# batteryholder2S6P_revD.net
KiCad netlist of a schematic drawn in EAGLE
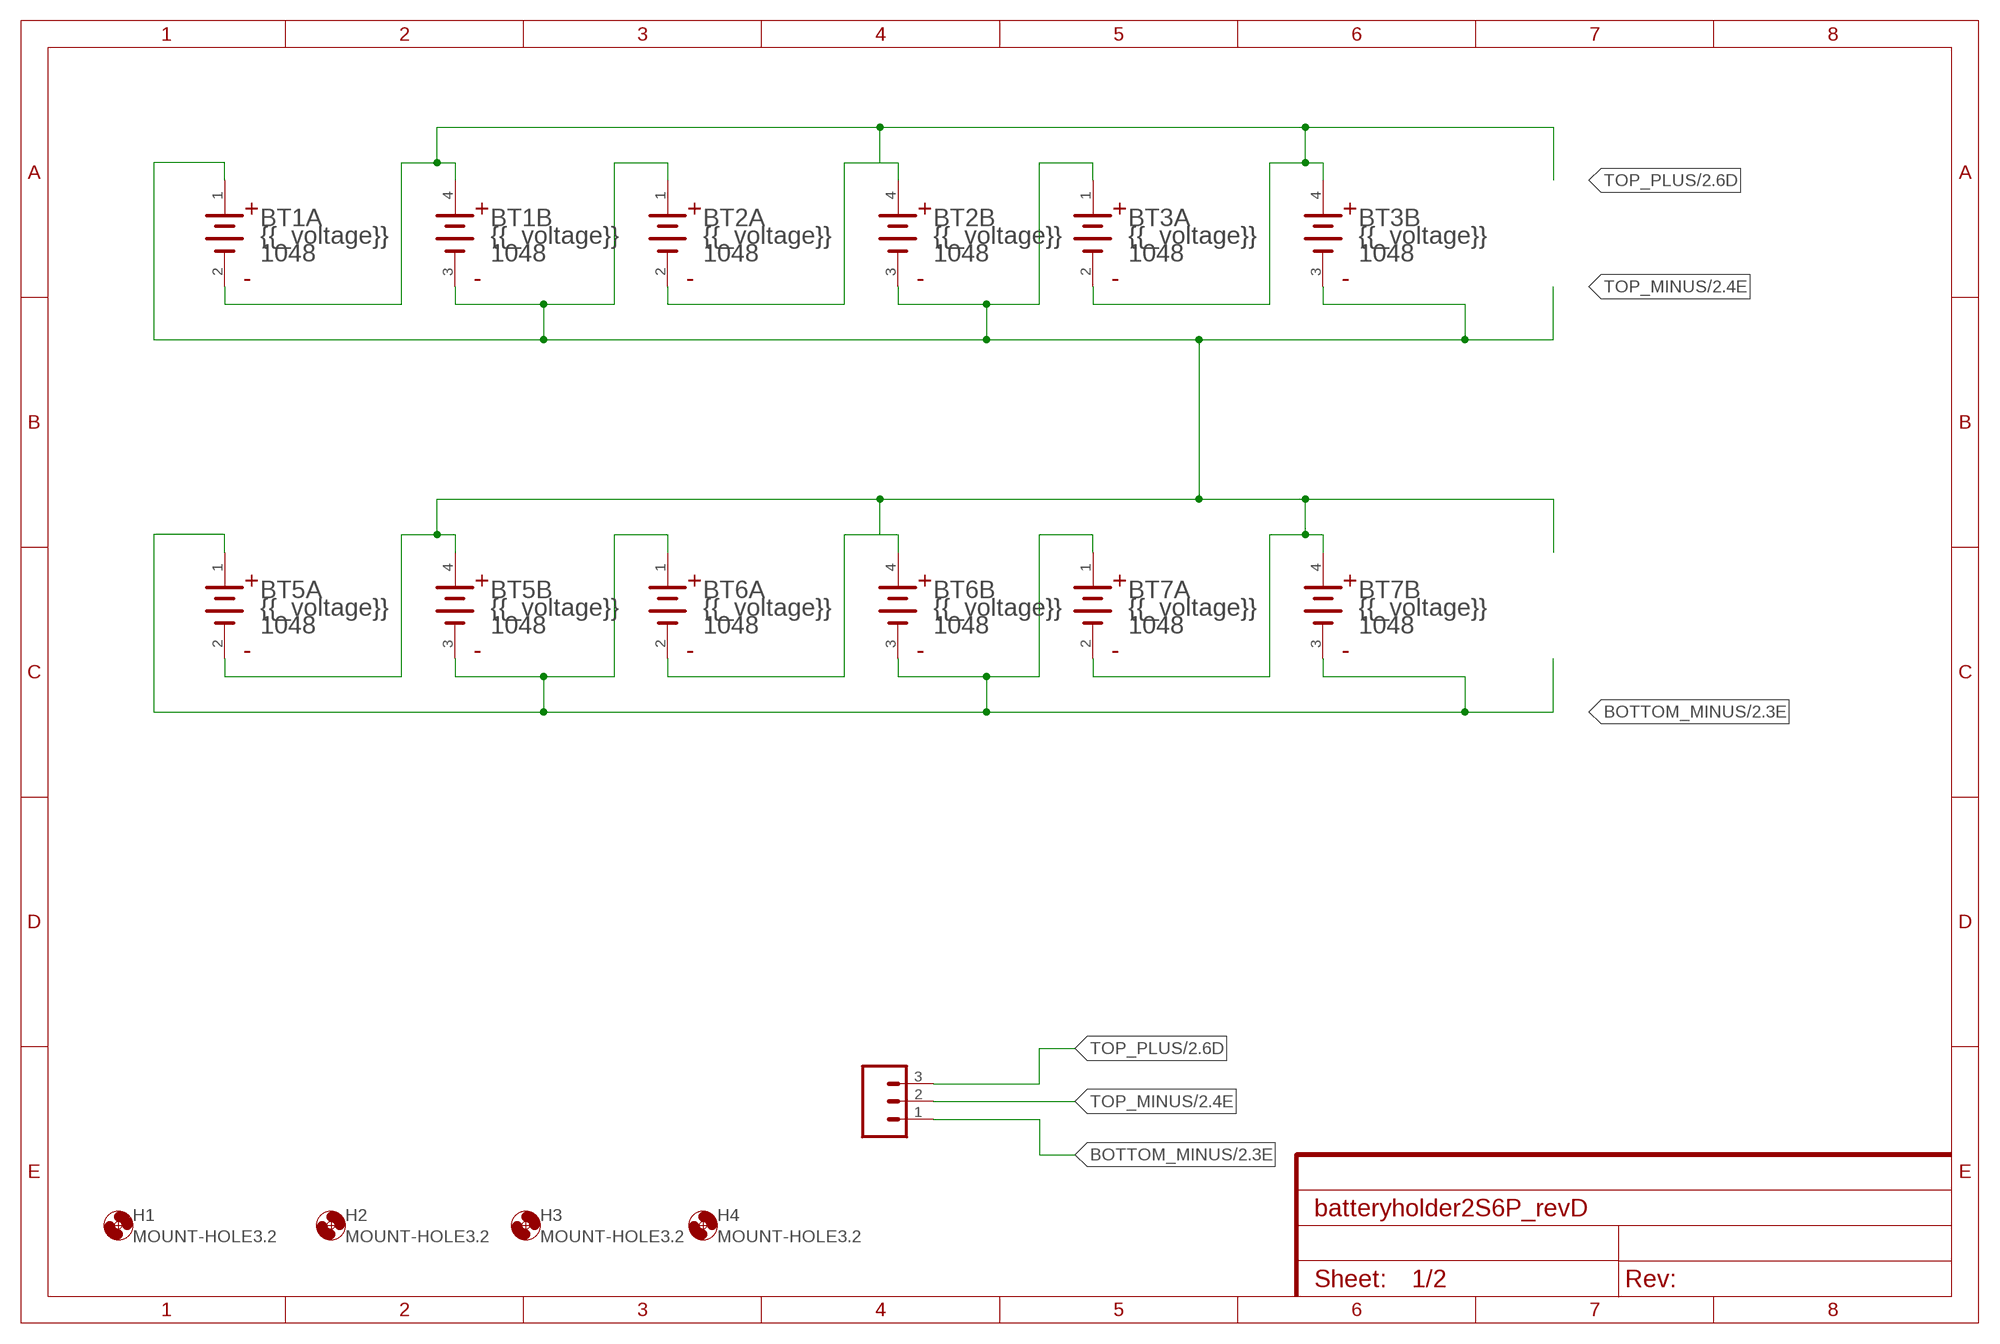
[diagram p0: schematic, sheet 1]
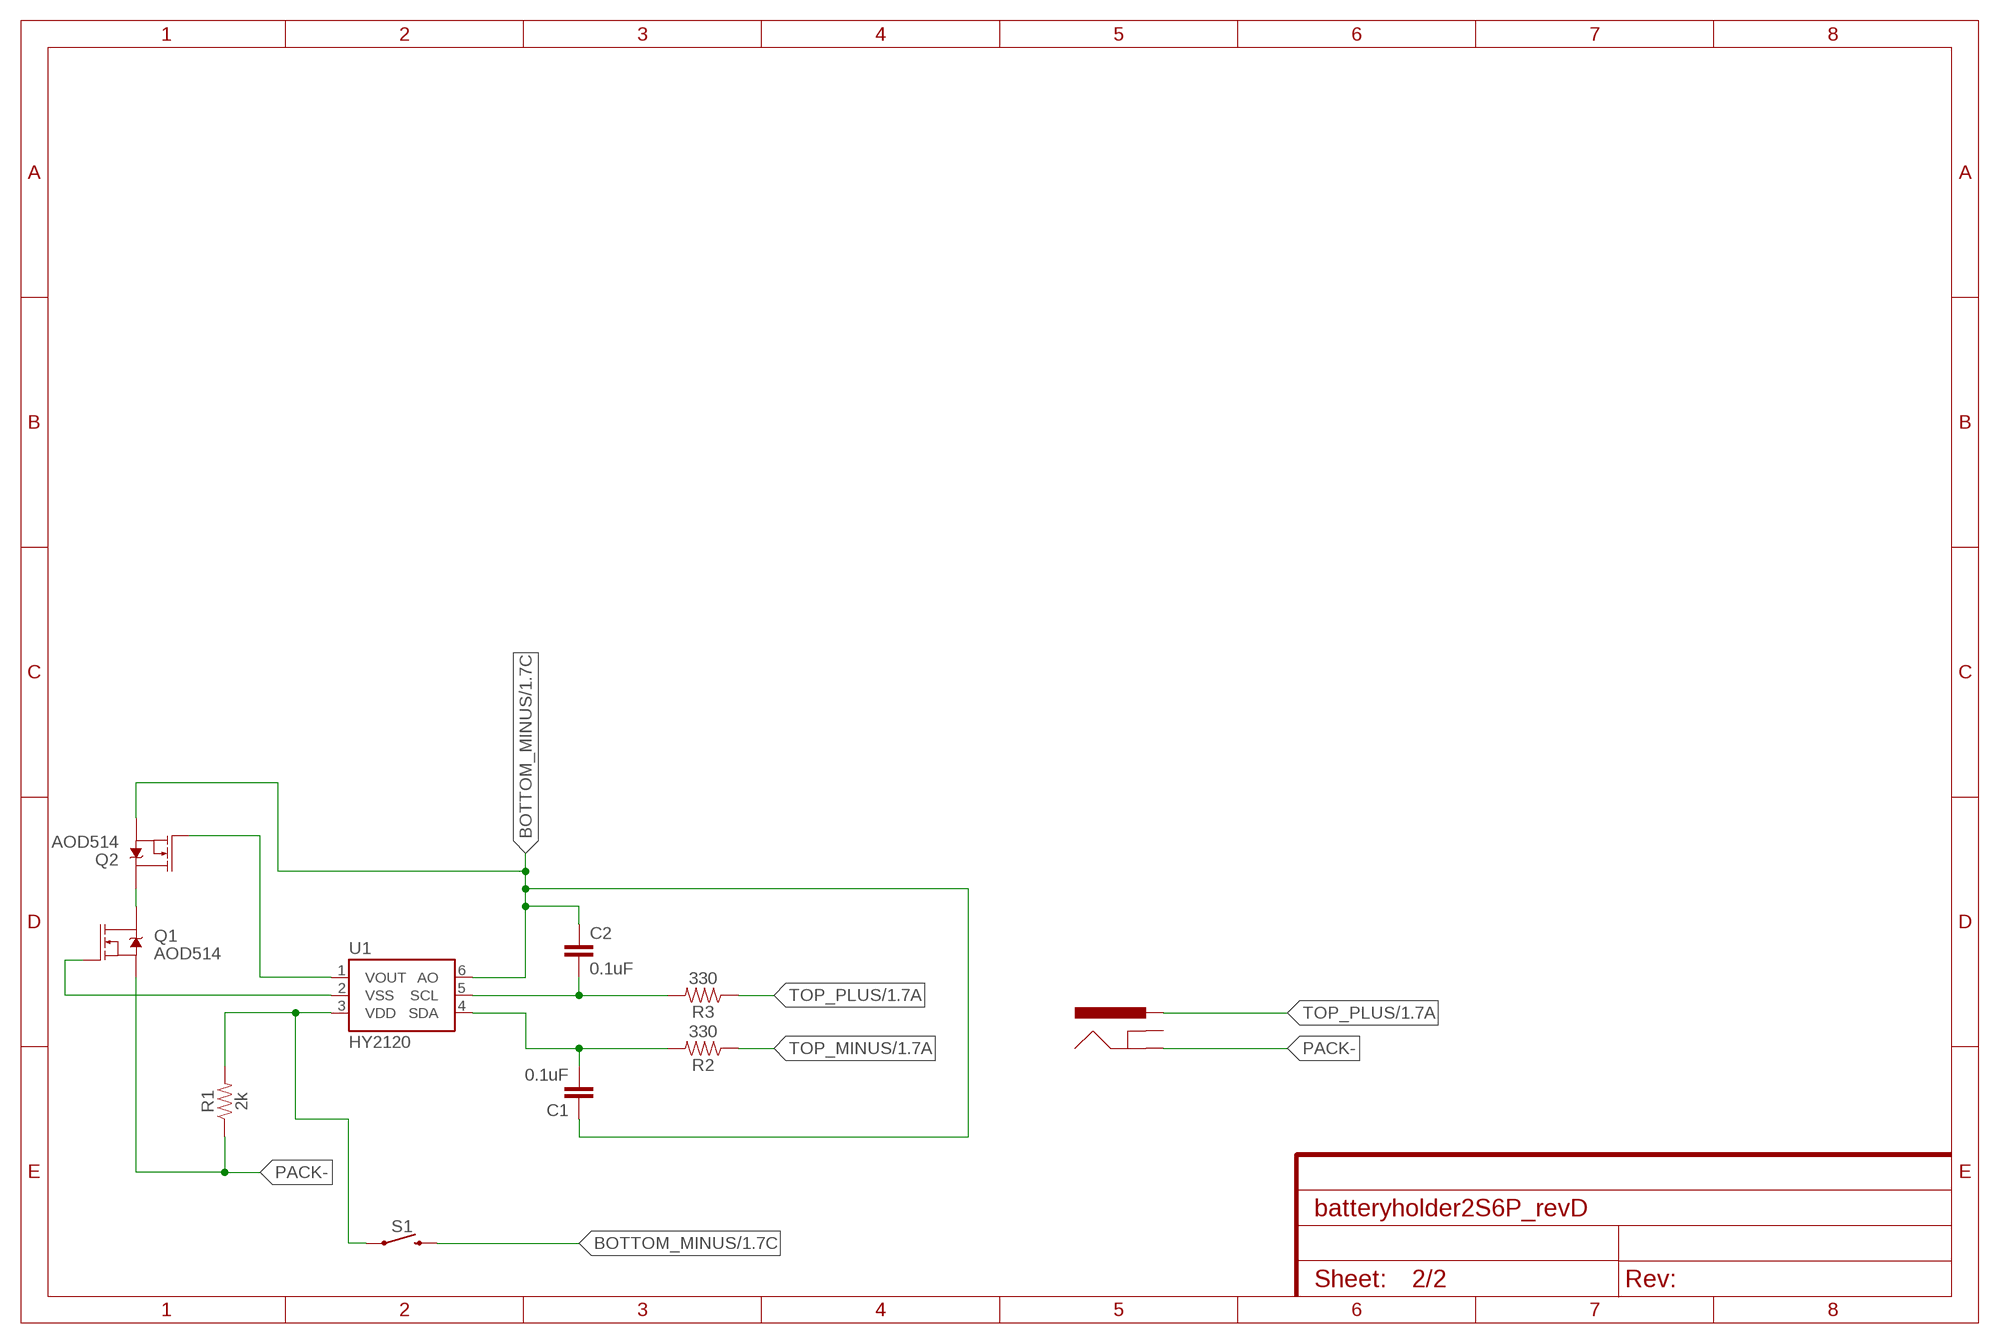
[diagram p1: schematic, sheet 2]

(export (version "E")
  (design (tool "Eeschema 10.0.6"))
  (components
    (comp (ref "C1")
      (value "0.1uF")
      (footprint "eagle-import:1206")
      (libsource (lib "eagle-import") (part "1.0UF-1206-50V-10%"))
    )
    (comp (ref "C2")
      (value "0.1uF")
      (footprint "eagle-import:1206")
      (libsource (lib "eagle-import") (part "1.0UF-1206-50V-10%"))
    )
    (comp (ref "J2")
      (value "POWER_JACKPTH_BREAD")
      (footprint "eagle-import:POWER_JACK_PTH_BREAD")
      (libsource (lib "eagle-import") (part "POWER_JACKPTH_BREAD"))
    )
    (comp (ref "Q1")
      (value "AOD514")
      (footprint "eagle-import:DPAK")
      (libsource (lib "eagle-import") (part "MOSFET-NCH-FDD8780"))
    )
    (comp (ref "Q2")
      (value "AOD514")
      (footprint "eagle-import:DPAK")
      (libsource (lib "eagle-import") (part "MOSFET-NCH-FDD8780"))
    )
    (comp (ref "R1")
      (value "2k")
      (footprint "eagle-import:1206")
      (libsource (lib "eagle-import") (part "RESISTOR1206"))
    )
    (comp (ref "R2")
      (value "330")
      (footprint "eagle-import:1206")
      (libsource (lib "eagle-import") (part "RESISTOR1206"))
    )
    (comp (ref "R3")
      (value "330")
      (footprint "eagle-import:1206")
      (libsource (lib "eagle-import") (part "RESISTOR1206"))
    )
    (comp (ref "S1")
      (value "MOMENTARY-SWITCH-SPST-PTH-6.0MM")
      (footprint "eagle-import:TACTILE_SWITCH_PTH_6.0MM")
      (libsource (lib "eagle-import") (part "MOMENTARY-SWITCH-SPST-PTH-6.0MM"))
    )
    (comp (ref "U1")
      (value "HY2120")
      (footprint "eagle-import:SOT23-6")
      (libsource (lib "eagle-import") (part "MCP4725SOT-23"))
    )
    (comp (ref "BT1")
      (value "KEYSTONE_1048KEYSTONE_1048_0_0")
      (footprint "eagle-import:KEYSTONE_1048_0")
      (fields
        (field (name "DIGIKEY_PART_NUMBER") "36-1048-ND")
        (field (name "MF") "Keystone")
        (field (name "MOUSER_PART_NUMBER") "534-1048")
      )
      (libsource (lib "eagle-import") (part "KEYSTONE_1048KEYSTONE_1048_0_0"))
    )
    (comp (ref "BT2")
      (value "KEYSTONE_1048KEYSTONE_1048_0_0")
      (footprint "eagle-import:KEYSTONE_1048_0")
      (fields
        (field (name "DIGIKEY_PART_NUMBER") "36-1048-ND")
        (field (name "MF") "Keystone")
        (field (name "MOUSER_PART_NUMBER") "534-1048")
      )
      (libsource (lib "eagle-import") (part "KEYSTONE_1048KEYSTONE_1048_0_0"))
    )
    (comp (ref "BT3")
      (value "KEYSTONE_1048KEYSTONE_1048_0_0")
      (footprint "eagle-import:KEYSTONE_1048_0")
      (fields
        (field (name "DIGIKEY_PART_NUMBER") "36-1048-ND")
        (field (name "MF") "Keystone")
        (field (name "MOUSER_PART_NUMBER") "534-1048")
      )
      (libsource (lib "eagle-import") (part "KEYSTONE_1048KEYSTONE_1048_0_0"))
    )
    (comp (ref "BT5")
      (value "KEYSTONE_1048KEYSTONE_1048_0_0")
      (footprint "eagle-import:KEYSTONE_1048_0")
      (fields
        (field (name "DIGIKEY_PART_NUMBER") "36-1048-ND")
        (field (name "MF") "Keystone")
        (field (name "MOUSER_PART_NUMBER") "534-1048")
      )
      (libsource (lib "eagle-import") (part "KEYSTONE_1048KEYSTONE_1048_0_0"))
    )
    (comp (ref "BT6")
      (value "KEYSTONE_1048KEYSTONE_1048_0_0")
      (footprint "eagle-import:KEYSTONE_1048_0")
      (fields
        (field (name "DIGIKEY_PART_NUMBER") "36-1048-ND")
        (field (name "MF") "Keystone")
        (field (name "MOUSER_PART_NUMBER") "534-1048")
      )
      (libsource (lib "eagle-import") (part "KEYSTONE_1048KEYSTONE_1048_0_0"))
    )
    (comp (ref "BT7")
      (value "KEYSTONE_1048KEYSTONE_1048_0_0")
      (footprint "eagle-import:KEYSTONE_1048_0")
      (fields
        (field (name "DIGIKEY_PART_NUMBER") "36-1048-ND")
        (field (name "MF") "Keystone")
        (field (name "MOUSER_PART_NUMBER") "534-1048")
      )
      (libsource (lib "eagle-import") (part "KEYSTONE_1048KEYSTONE_1048_0_0"))
    )
    (comp (ref "H1")
      (value "MOUNT-HOLE3.2")
      (footprint "eagle-import:3,2")
      (libsource (lib "eagle-import") (part "MOUNT-HOLE3.2"))
    )
    (comp (ref "H2")
      (value "MOUNT-HOLE3.2")
      (footprint "eagle-import:3,2")
      (libsource (lib "eagle-import") (part "MOUNT-HOLE3.2"))
    )
    (comp (ref "H3")
      (value "MOUNT-HOLE3.2")
      (footprint "eagle-import:3,2")
      (libsource (lib "eagle-import") (part "MOUNT-HOLE3.2"))
    )
    (comp (ref "H4")
      (value "MOUNT-HOLE3.2")
      (footprint "eagle-import:3,2")
      (libsource (lib "eagle-import") (part "MOUNT-HOLE3.2"))
    )
    (comp (ref "J1")
      (value "CONN_03-SCREW-5MM")
      (footprint "eagle-import:SCREWTERMINAL-5MM-3")
      (libsource (lib "eagle-import") (part "CONN_03-SCREW-5MM"))
    )
  )
  (nets
    (net (code "1") (name "BOTTOM_MINUS") (class "Default")
      (node (ref "BT5") (pin "1") (pinfunction "1_ANODE_1") (pintype "passive"))
      (node (ref "BT5") (pin "3") (pinfunction "2_CATHODE_3") (pintype "passive"))
      (node (ref "BT6") (pin "1") (pinfunction "1_ANODE_1") (pintype "passive"))
      (node (ref "BT6") (pin "3") (pinfunction "2_CATHODE_3") (pintype "passive"))
      (node (ref "BT7") (pin "1") (pinfunction "1_ANODE_1") (pintype "passive"))
      (node (ref "BT7") (pin "3") (pinfunction "2_CATHODE_3") (pintype "passive"))
      (node (ref "C1") (pin "1") (pinfunction "1_1") (pintype "passive"))
      (node (ref "C2") (pin "1") (pinfunction "1_1") (pintype "passive"))
      (node (ref "J1") (pin "1") (pinfunction "1_1") (pintype "passive"))
      (node (ref "Q2") (pin "3") (pinfunction "S_3") (pintype "bidirectional"))
      (node (ref "S1") (pin "3") (pinfunction "2_3") (pintype "passive"))
      (node (ref "U1") (pin "6") (pinfunction "AO_6") (pintype "bidirectional"))
    )
    (net (code "2") (name "Net-(Q1-D)") (class "Default")
      (node (ref "Q1") (pin "4") (pinfunction "D_4") (pintype "bidirectional"))
      (node (ref "Q2") (pin "4") (pinfunction "D_4") (pintype "bidirectional"))
    )
    (net (code "3") (name "Net-(Q1-G)") (class "Default")
      (node (ref "Q1") (pin "1") (pinfunction "G_1") (pintype "bidirectional"))
      (node (ref "U1") (pin "2") (pinfunction "VSS_2") (pintype "bidirectional"))
    )
    (net (code "4") (name "Net-(Q2-G)") (class "Default")
      (node (ref "Q2") (pin "1") (pinfunction "G_1") (pintype "bidirectional"))
      (node (ref "U1") (pin "1") (pinfunction "VOUT_1") (pintype "bidirectional"))
    )
    (net (code "5") (name "Net-(U1-SCL)") (class "Default")
      (node (ref "C2") (pin "2") (pinfunction "2_2") (pintype "passive"))
      (node (ref "R3") (pin "2") (pinfunction "2_2") (pintype "passive"))
      (node (ref "U1") (pin "5") (pinfunction "SCL_5") (pintype "bidirectional"))
    )
    (net (code "6") (name "Net-(U1-SDA)") (class "Default")
      (node (ref "C1") (pin "2") (pinfunction "2_2") (pintype "passive"))
      (node (ref "R2") (pin "2") (pinfunction "2_2") (pintype "passive"))
      (node (ref "U1") (pin "4") (pinfunction "SDA_4") (pintype "bidirectional"))
    )
    (net (code "7") (name "Net-(U1-VDD)") (class "Default")
      (node (ref "R1") (pin "2") (pinfunction "2_2") (pintype "passive"))
      (node (ref "S1") (pin "1") (pinfunction "1_1") (pintype "passive"))
      (node (ref "U1") (pin "3") (pinfunction "VDD_3") (pintype "bidirectional"))
    )
    (net (code "8") (name "PACK-") (class "Default")
      (node (ref "J2") (pin "GND") (pinfunction "GND_GND") (pintype "bidirectional"))
      (node (ref "Q1") (pin "3") (pinfunction "S_3") (pintype "bidirectional"))
      (node (ref "R1") (pin "1") (pinfunction "1_1") (pintype "passive"))
    )
    (net (code "9") (name "TOP_MINUS") (class "Default")
      (node (ref "BT1") (pin "1") (pinfunction "1_ANODE_1") (pintype "passive"))
      (node (ref "BT1") (pin "3") (pinfunction "2_CATHODE_3") (pintype "passive"))
      (node (ref "BT2") (pin "1") (pinfunction "1_ANODE_1") (pintype "passive"))
      (node (ref "BT2") (pin "3") (pinfunction "2_CATHODE_3") (pintype "passive"))
      (node (ref "BT3") (pin "1") (pinfunction "1_ANODE_1") (pintype "passive"))
      (node (ref "BT3") (pin "3") (pinfunction "2_CATHODE_3") (pintype "passive"))
      (node (ref "BT5") (pin "2") (pinfunction "1_CATHODE_2") (pintype "passive"))
      (node (ref "BT5") (pin "4") (pinfunction "2_ANODE_4") (pintype "passive"))
      (node (ref "BT6") (pin "2") (pinfunction "1_CATHODE_2") (pintype "passive"))
      (node (ref "BT6") (pin "4") (pinfunction "2_ANODE_4") (pintype "passive"))
      (node (ref "BT7") (pin "2") (pinfunction "1_CATHODE_2") (pintype "passive"))
      (node (ref "BT7") (pin "4") (pinfunction "2_ANODE_4") (pintype "passive"))
      (node (ref "J1") (pin "2") (pinfunction "2_2") (pintype "passive"))
      (node (ref "R2") (pin "1") (pinfunction "1_1") (pintype "passive"))
    )
    (net (code "10") (name "TOP_PLUS") (class "Default")
      (node (ref "BT1") (pin "2") (pinfunction "1_CATHODE_2") (pintype "passive"))
      (node (ref "BT1") (pin "4") (pinfunction "2_ANODE_4") (pintype "passive"))
      (node (ref "BT2") (pin "2") (pinfunction "1_CATHODE_2") (pintype "passive"))
      (node (ref "BT2") (pin "4") (pinfunction "2_ANODE_4") (pintype "passive"))
      (node (ref "BT3") (pin "2") (pinfunction "1_CATHODE_2") (pintype "passive"))
      (node (ref "BT3") (pin "4") (pinfunction "2_ANODE_4") (pintype "passive"))
      (node (ref "J1") (pin "3") (pinfunction "3_3") (pintype "passive"))
      (node (ref "J2") (pin "PWR") (pinfunction "PWR_PWR") (pintype "bidirectional"))
      (node (ref "R3") (pin "1") (pinfunction "1_1") (pintype "passive"))
    )
    (net (code "11") (name "unconnected-(J2-PadGNDBREAK)") (class "Default")
      (node (ref "J2") (pin "GNDBREAK") (pinfunction "GNDBREAK_GNDBREAK") (pintype "bidirectional"))
    )
  )
)
